# Plata_Perehodnaya.net
KiCad netlist of a schematic drawn in Altium Designer
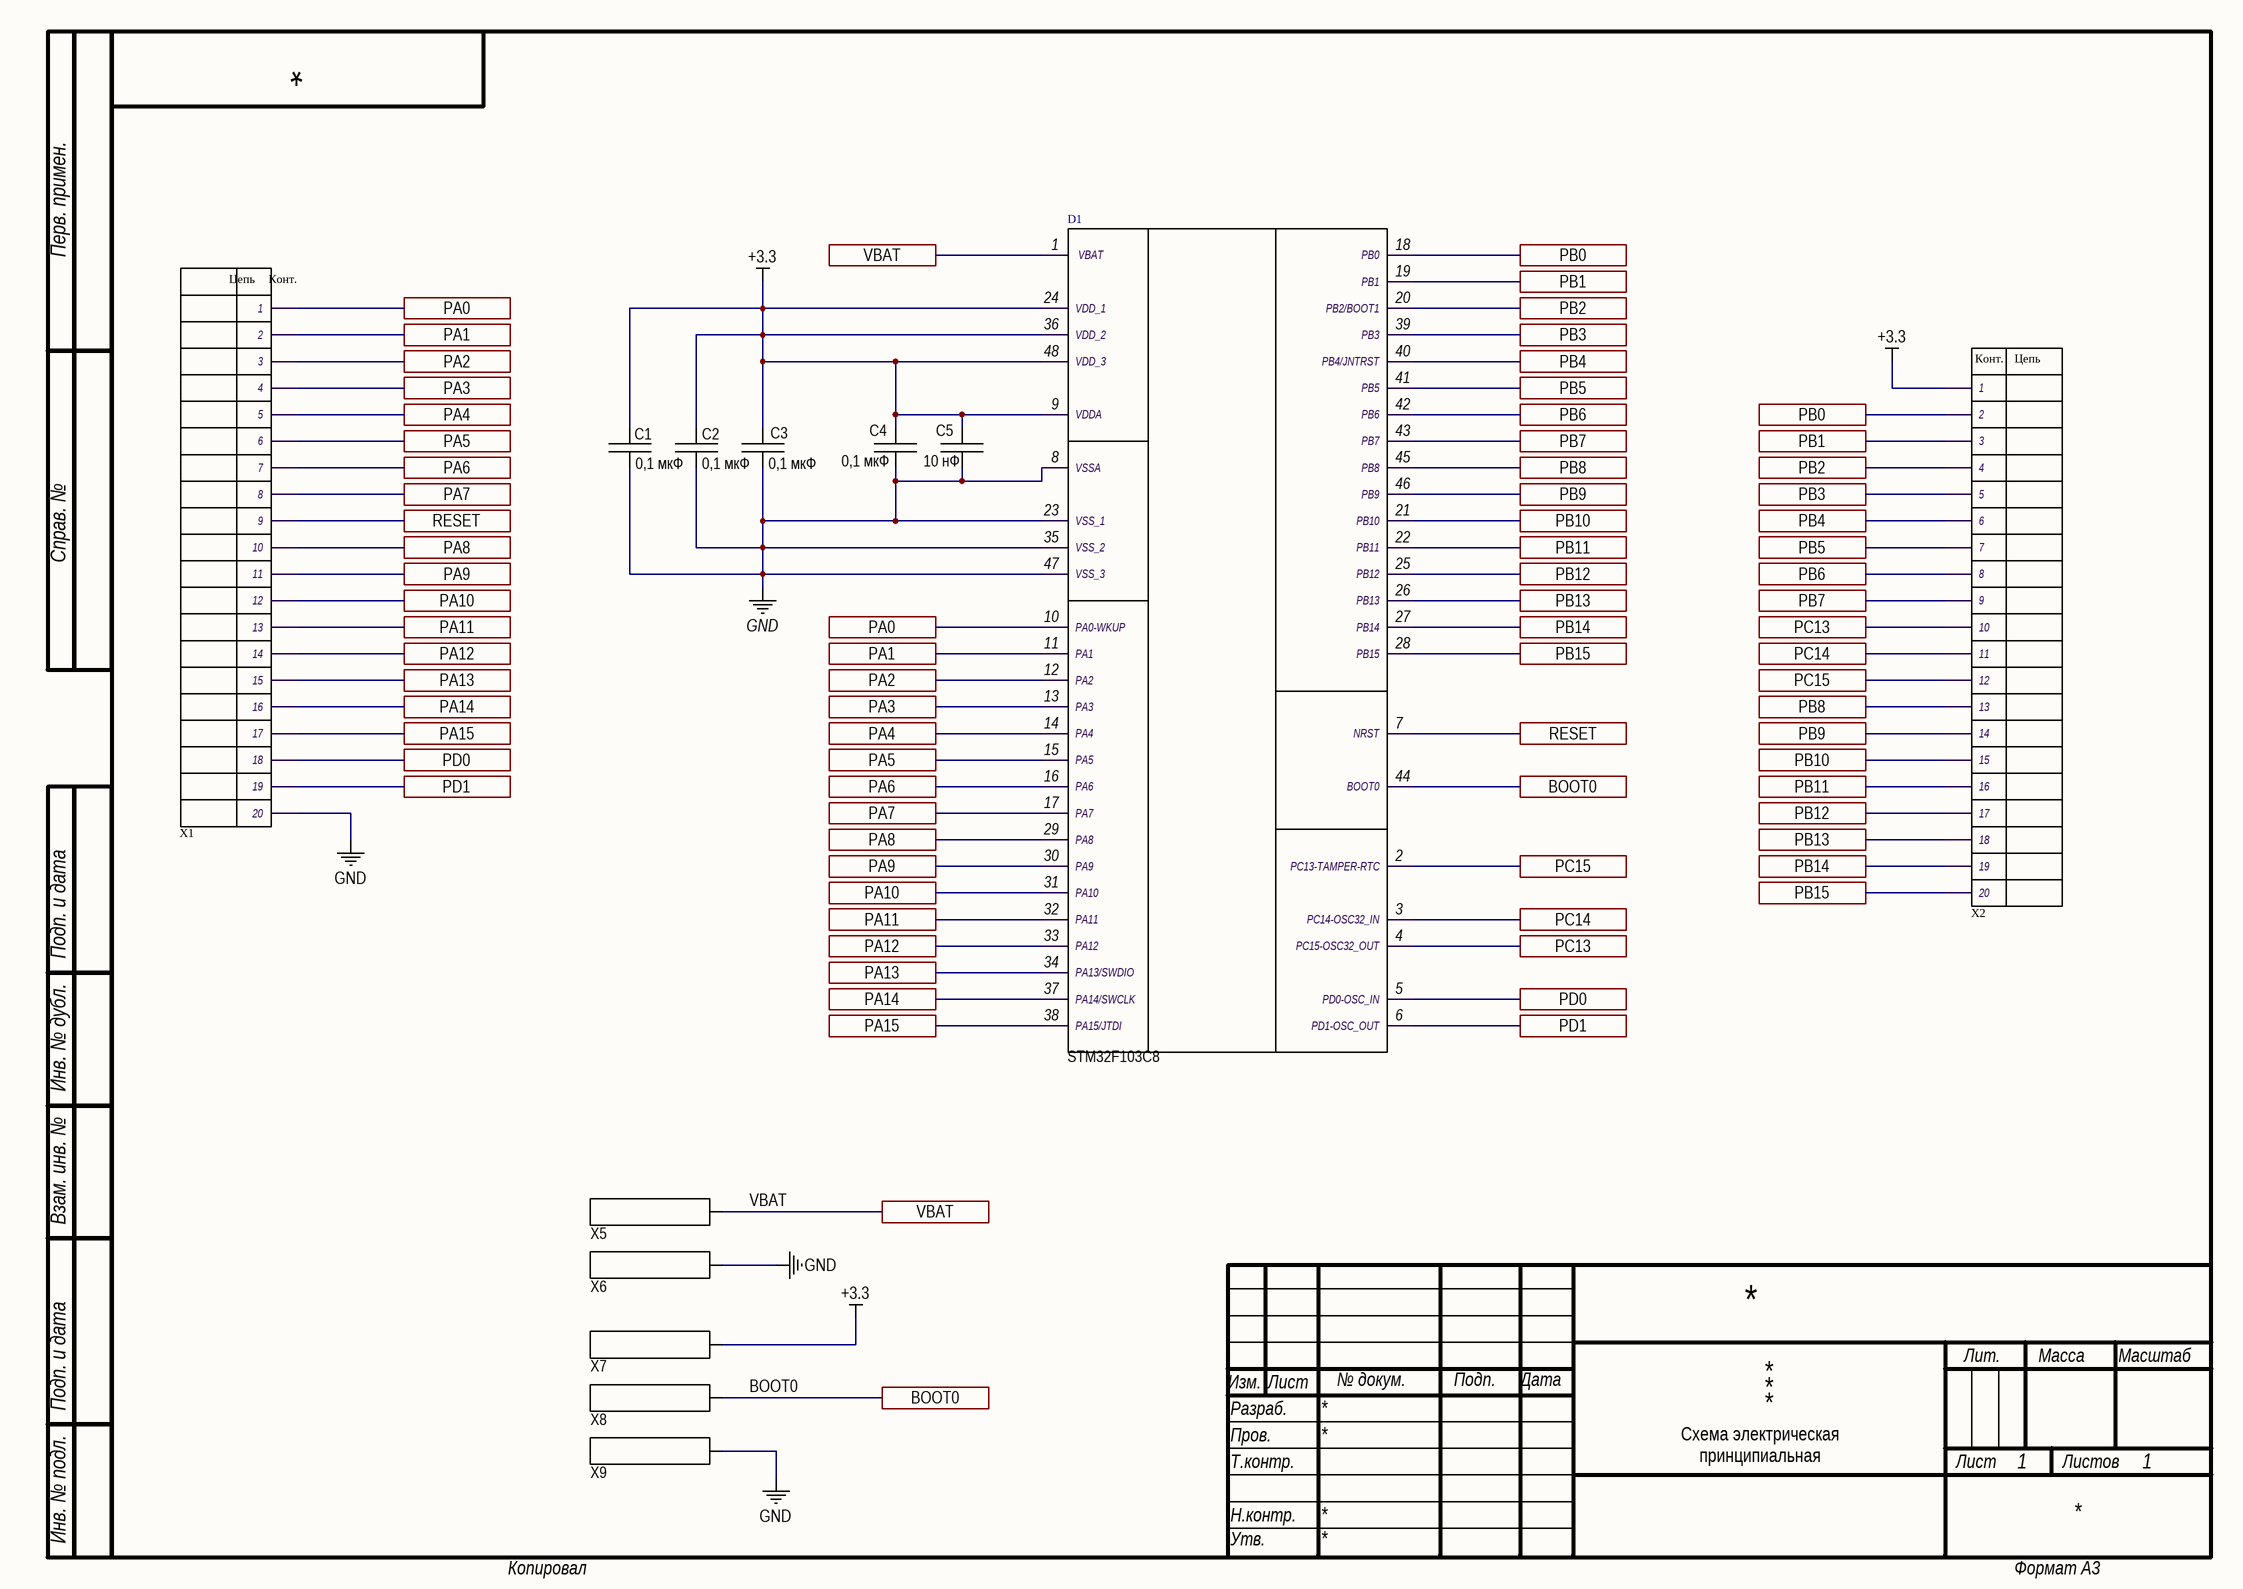
[diagram p0: Plata_Perehodnaya.SchDoc]

(export (version "E")
  (design (tool "Eeschema 10.0.6"))
  (components
    (comp (ref "C1")
      (value "0,1 мкФ")
      (footprint "C0805")
      (description "0.1 µF ±10% 50V Ceramic Capacitor X7R 0805 (2012 Metric)")
      (libsource (lib "Capacitors") (part "Capacity"))
    )
    (comp (ref "C2")
      (value "0,1 мкФ")
      (footprint "C0805")
      (description "0.1 µF ±10% 50V Ceramic Capacitor X7R 0805 (2012 Metric)")
      (libsource (lib "Capacitors") (part "Capacity"))
    )
    (comp (ref "C3")
      (value "0,1 мкФ")
      (footprint "C0805")
      (description "0.1 µF ±10% 50V Ceramic Capacitor X7R 0805 (2012 Metric)")
      (libsource (lib "Capacitors") (part "Capacity"))
    )
    (comp (ref "C4")
      (value "0,1 мкФ")
      (footprint "C0805")
      (description "0.1 µF ±10% 50V Ceramic Capacitor X7R 0805 (2012 Metric)")
      (libsource (lib "Capacitors") (part "Capacity"))
    )
    (comp (ref "C5")
      (value "10 нФ")
      (footprint "C0805")
      (description "±5% 50V Ceramic Capacitor X7R 0805 (2012 Metric)")
      (libsource (lib "Capacitors") (part "Capacity"))
    )
    (comp (ref "D1")
      (value "STM32F103C8")
      (footprint "48-LQFP (7x7)")
      (libsource (lib "Microcontroller") (part "STM32F103C8T6"))
    )
    (comp (ref "X1")
      (value "*")
      (footprint "PLS-20 (DS-1021-1x20)")
      (libsource (lib "") (part "Разъемы на плате-20_1"))
    )
    (comp (ref "X2")
      (value "*")
      (footprint "PLS-20 (DS-1021-1x20)")
      (libsource (lib "Connectors") (part "Разъемы на плате-20"))
    )
    (comp (ref "X5")
      (value "Стыковка")
      (footprint "Стыковка")
      (libsource (lib "Connectors") (part "Стыковка"))
    )
    (comp (ref "X6")
      (value "Стыковка")
      (footprint "Стыковка")
      (libsource (lib "Connectors") (part "Стыковка"))
    )
    (comp (ref "X7")
      (value "Стыковка")
      (footprint "Стыковка")
      (libsource (lib "Connectors") (part "Стыковка"))
    )
    (comp (ref "X8")
      (value "Стыковка")
      (footprint "Стыковка")
      (libsource (lib "Connectors") (part "Стыковка"))
    )
    (comp (ref "X9")
      (value "Стыковка")
      (footprint "Стыковка")
      (libsource (lib "Connectors") (part "Стыковка"))
    )
  )
  (nets
    (net (code "1") (name "+3.3") (class "Default")
      (node (ref "C1") (pin "1") (pinfunction "1_1") (pintype "passive"))
      (node (ref "C2") (pin "1") (pinfunction "1_1") (pintype "passive"))
      (node (ref "C3") (pin "1") (pinfunction "1_1") (pintype "passive"))
      (node (ref "C4") (pin "1") (pinfunction "1_1") (pintype "passive"))
      (node (ref "C5") (pin "1") (pinfunction "1_1") (pintype "passive"))
      (node (ref "D1") (pin "24") (pinfunction "VDD_1_24") (pintype "passive"))
      (node (ref "D1") (pin "36") (pinfunction "VDD_2_36") (pintype "passive"))
      (node (ref "D1") (pin "48") (pinfunction "VDD_3_48") (pintype "passive"))
      (node (ref "D1") (pin "9") (pinfunction "VDDA_9") (pintype "passive"))
      (node (ref "X2") (pin "1") (pinfunction "1_1") (pintype "passive"))
      (node (ref "X7") (pin "1") (pinfunction "1_1") (pintype "passive"))
    )
    (net (code "2") (name "/BOOT0") (class "Default")
      (node (ref "D1") (pin "44") (pinfunction "BOOT0_44") (pintype "passive"))
      (node (ref "X8") (pin "1") (pinfunction "1_1") (pintype "passive"))
    )
    (net (code "3") (name "/PA0") (class "Default")
      (node (ref "D1") (pin "10") (pinfunction "PA0-WKUP_10") (pintype "passive"))
      (node (ref "X1") (pin "1") (pinfunction "1_1") (pintype "passive"))
    )
    (net (code "4") (name "/PA1") (class "Default")
      (node (ref "D1") (pin "11") (pinfunction "PA1_11") (pintype "passive"))
      (node (ref "X1") (pin "2") (pinfunction "2_2") (pintype "passive"))
    )
    (net (code "5") (name "/PA2") (class "Default")
      (node (ref "D1") (pin "12") (pinfunction "PA2_12") (pintype "passive"))
      (node (ref "X1") (pin "3") (pinfunction "3_3") (pintype "passive"))
    )
    (net (code "6") (name "/PA3") (class "Default")
      (node (ref "D1") (pin "13") (pinfunction "PA3_13") (pintype "passive"))
      (node (ref "X1") (pin "4") (pinfunction "4_4") (pintype "passive"))
    )
    (net (code "7") (name "/PA4") (class "Default")
      (node (ref "D1") (pin "14") (pinfunction "PA4_14") (pintype "passive"))
      (node (ref "X1") (pin "5") (pinfunction "5_5") (pintype "passive"))
    )
    (net (code "8") (name "/PA5") (class "Default")
      (node (ref "D1") (pin "15") (pinfunction "PA5_15") (pintype "passive"))
      (node (ref "X1") (pin "6") (pinfunction "6_6") (pintype "passive"))
    )
    (net (code "9") (name "/PA6") (class "Default")
      (node (ref "D1") (pin "16") (pinfunction "PA6_16") (pintype "passive"))
      (node (ref "X1") (pin "7") (pinfunction "7_7") (pintype "passive"))
    )
    (net (code "10") (name "/PA7") (class "Default")
      (node (ref "D1") (pin "17") (pinfunction "PA7_17") (pintype "passive"))
      (node (ref "X1") (pin "8") (pinfunction "8_8") (pintype "passive"))
    )
    (net (code "11") (name "/PA8") (class "Default")
      (node (ref "D1") (pin "29") (pinfunction "PA8_29") (pintype "passive"))
      (node (ref "X1") (pin "10") (pinfunction "10_10") (pintype "passive"))
    )
    (net (code "12") (name "/PA9") (class "Default")
      (node (ref "D1") (pin "30") (pinfunction "PA9_30") (pintype "passive"))
      (node (ref "X1") (pin "11") (pinfunction "11_11") (pintype "passive"))
    )
    (net (code "13") (name "/PA10") (class "Default")
      (node (ref "D1") (pin "31") (pinfunction "PA10_31") (pintype "passive"))
      (node (ref "X1") (pin "12") (pinfunction "12_12") (pintype "passive"))
    )
    (net (code "14") (name "/PA11") (class "Default")
      (node (ref "D1") (pin "32") (pinfunction "PA11_32") (pintype "passive"))
      (node (ref "X1") (pin "13") (pinfunction "13_13") (pintype "passive"))
    )
    (net (code "15") (name "/PA12") (class "Default")
      (node (ref "D1") (pin "33") (pinfunction "PA12_33") (pintype "passive"))
      (node (ref "X1") (pin "14") (pinfunction "14_14") (pintype "passive"))
    )
    (net (code "16") (name "/PA13") (class "Default")
      (node (ref "D1") (pin "34") (pinfunction "PA13/SWDIO_34") (pintype "passive"))
      (node (ref "X1") (pin "15") (pinfunction "15_15") (pintype "passive"))
    )
    (net (code "17") (name "/PA14") (class "Default")
      (node (ref "D1") (pin "37") (pinfunction "PA14/SWCLK_37") (pintype "passive"))
      (node (ref "X1") (pin "16") (pinfunction "16_16") (pintype "passive"))
    )
    (net (code "18") (name "/PA15") (class "Default")
      (node (ref "D1") (pin "38") (pinfunction "PA15/JTDI_38") (pintype "passive"))
      (node (ref "X1") (pin "17") (pinfunction "17_17") (pintype "passive"))
    )
    (net (code "19") (name "/PB0") (class "Default")
      (node (ref "D1") (pin "18") (pinfunction "PB0_18") (pintype "passive"))
      (node (ref "X2") (pin "2") (pinfunction "2_2") (pintype "passive"))
    )
    (net (code "20") (name "/PB1") (class "Default")
      (node (ref "D1") (pin "19") (pinfunction "PB1_19") (pintype "passive"))
      (node (ref "X2") (pin "3") (pinfunction "3_3") (pintype "passive"))
    )
    (net (code "21") (name "/PB2") (class "Default")
      (node (ref "D1") (pin "20") (pinfunction "PB2/BOOT1_20") (pintype "passive"))
      (node (ref "X2") (pin "4") (pinfunction "4_4") (pintype "passive"))
    )
    (net (code "22") (name "/PB3") (class "Default")
      (node (ref "D1") (pin "39") (pinfunction "PB3_39") (pintype "passive"))
      (node (ref "X2") (pin "5") (pinfunction "5_5") (pintype "passive"))
    )
    (net (code "23") (name "/PB4") (class "Default")
      (node (ref "D1") (pin "40") (pinfunction "PB4/JNTRST_40") (pintype "passive"))
      (node (ref "X2") (pin "6") (pinfunction "6_6") (pintype "passive"))
    )
    (net (code "24") (name "/PB5") (class "Default")
      (node (ref "D1") (pin "41") (pinfunction "PB5_41") (pintype "passive"))
      (node (ref "X2") (pin "7") (pinfunction "7_7") (pintype "passive"))
    )
    (net (code "25") (name "/PB6") (class "Default")
      (node (ref "D1") (pin "42") (pinfunction "PB6_42") (pintype "passive"))
      (node (ref "X2") (pin "8") (pinfunction "8_8") (pintype "passive"))
    )
    (net (code "26") (name "/PB7") (class "Default")
      (node (ref "D1") (pin "43") (pinfunction "PB7_43") (pintype "passive"))
      (node (ref "X2") (pin "9") (pinfunction "9_9") (pintype "passive"))
    )
    (net (code "27") (name "/PB8") (class "Default")
      (node (ref "D1") (pin "45") (pinfunction "PB8_45") (pintype "passive"))
      (node (ref "X2") (pin "13") (pinfunction "13_13") (pintype "passive"))
    )
    (net (code "28") (name "/PB9") (class "Default")
      (node (ref "D1") (pin "46") (pinfunction "PB9_46") (pintype "passive"))
      (node (ref "X2") (pin "14") (pinfunction "14_14") (pintype "passive"))
    )
    (net (code "29") (name "/PB10") (class "Default")
      (node (ref "D1") (pin "21") (pinfunction "PB10_21") (pintype "passive"))
      (node (ref "X2") (pin "15") (pinfunction "15_15") (pintype "passive"))
    )
    (net (code "30") (name "/PB11") (class "Default")
      (node (ref "D1") (pin "22") (pinfunction "PB11_22") (pintype "passive"))
      (node (ref "X2") (pin "16") (pinfunction "16_16") (pintype "passive"))
    )
    (net (code "31") (name "/PB12") (class "Default")
      (node (ref "D1") (pin "25") (pinfunction "PB12_25") (pintype "passive"))
      (node (ref "X2") (pin "17") (pinfunction "17_17") (pintype "passive"))
    )
    (net (code "32") (name "/PB13") (class "Default")
      (node (ref "D1") (pin "26") (pinfunction "PB13_26") (pintype "passive"))
      (node (ref "X2") (pin "18") (pinfunction "18_18") (pintype "passive"))
    )
    (net (code "33") (name "/PB14") (class "Default")
      (node (ref "D1") (pin "27") (pinfunction "PB14_27") (pintype "passive"))
      (node (ref "X2") (pin "19") (pinfunction "19_19") (pintype "passive"))
    )
    (net (code "34") (name "/PB15") (class "Default")
      (node (ref "D1") (pin "28") (pinfunction "PB15_28") (pintype "passive"))
      (node (ref "X2") (pin "20") (pinfunction "20_20") (pintype "passive"))
    )
    (net (code "35") (name "/PC13") (class "Default")
      (node (ref "D1") (pin "4") (pinfunction "PC15-OSC32_OUT_4") (pintype "passive"))
      (node (ref "X2") (pin "10") (pinfunction "10_10") (pintype "passive"))
    )
    (net (code "36") (name "/PC14") (class "Default")
      (node (ref "D1") (pin "3") (pinfunction "PC14-OSC32_IN_3") (pintype "passive"))
      (node (ref "X2") (pin "11") (pinfunction "11_11") (pintype "passive"))
    )
    (net (code "37") (name "/PC15") (class "Default")
      (node (ref "D1") (pin "2") (pinfunction "PC13-TAMPER-RTC_2") (pintype "passive"))
      (node (ref "X2") (pin "12") (pinfunction "12_12") (pintype "passive"))
    )
    (net (code "38") (name "/PD0") (class "Default")
      (node (ref "D1") (pin "5") (pinfunction "PD0-OSC_IN_5") (pintype "passive"))
      (node (ref "X1") (pin "18") (pinfunction "18_18") (pintype "passive"))
    )
    (net (code "39") (name "/PD1") (class "Default")
      (node (ref "D1") (pin "6") (pinfunction "PD1-OSC_OUT_6") (pintype "passive"))
      (node (ref "X1") (pin "19") (pinfunction "19_19") (pintype "passive"))
    )
    (net (code "40") (name "/RESET") (class "Default")
      (node (ref "D1") (pin "7") (pinfunction "NRST_7") (pintype "passive"))
      (node (ref "X1") (pin "9") (pinfunction "9_9") (pintype "passive"))
    )
    (net (code "41") (name "/VBAT") (class "Default")
      (node (ref "D1") (pin "1") (pinfunction "_VBAT_1") (pintype "passive"))
      (node (ref "X5") (pin "1") (pinfunction "1_1") (pintype "passive"))
    )
    (net (code "42") (name "GND") (class "Default")
      (node (ref "C1") (pin "2") (pinfunction "2_2") (pintype "passive"))
      (node (ref "C2") (pin "2") (pinfunction "2_2") (pintype "passive"))
      (node (ref "C3") (pin "2") (pinfunction "2_2") (pintype "passive"))
      (node (ref "C4") (pin "2") (pinfunction "2_2") (pintype "passive"))
      (node (ref "C5") (pin "2") (pinfunction "2_2") (pintype "passive"))
      (node (ref "D1") (pin "23") (pinfunction "VSS_1_23") (pintype "passive"))
      (node (ref "D1") (pin "35") (pinfunction "VSS_2_35") (pintype "passive"))
      (node (ref "D1") (pin "47") (pinfunction "VSS_3_47") (pintype "passive"))
      (node (ref "D1") (pin "8") (pinfunction "VSSA_8") (pintype "passive"))
      (node (ref "X1") (pin "20") (pinfunction "20_20") (pintype "passive"))
      (node (ref "X6") (pin "1") (pinfunction "1_1") (pintype "passive"))
      (node (ref "X9") (pin "1") (pinfunction "1_1") (pintype "passive"))
    )
  )
)
